# Sheet_1_2022-03-10.net
KiCad netlist of a schematic drawn in Altium Designer
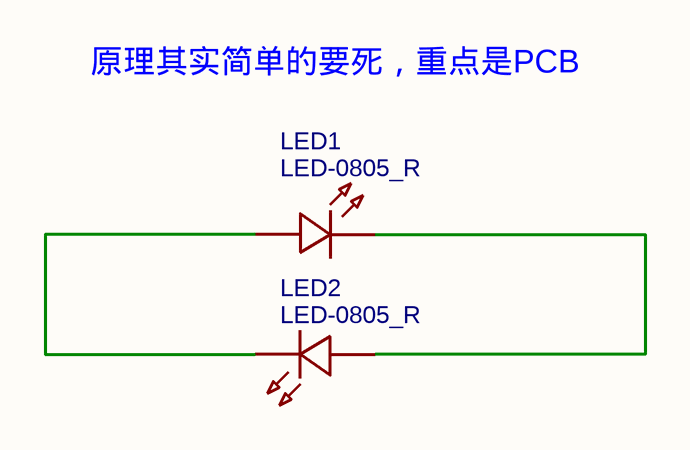
[diagram p0: Sheet_1_2022-03-10.schdoc]

(export (version "E")
  (design (tool "Eeschema 10.0.6"))
  (components
    (comp (ref "LED1")
      (value "LED-0805_R")
      (fields
        (field (name "BOM_MANUFACTURER PART") "17-21SURC/S530-A3/TR8")
        (field (name "BOM_SUPPLIER PART") "C72037")
        (field (name "CONTRIBUTOR") "LCEDA_Lib")
      )
      (libsource (lib "altium-import") (part "root_0_LED-0805_R_"))
    )
    (comp (ref "LED2")
      (value "LED-0805_R")
      (fields
        (field (name "BOM_MANUFACTURER PART") "17-21SURC/S530-A3/TR8")
        (field (name "BOM_SUPPLIER PART") "C72037")
        (field (name "CONTRIBUTOR") "LCEDA_Lib")
      )
      (libsource (lib "altium-import") (part "root_2_LED-0805_R_"))
    )
  )
  (nets
    (net (code "1") (name "Net-(LED1-Pad1)") (class "Default")
      (node (ref "LED1") (pin "1") (pinfunction "1_1") (pintype "passive"))
      (node (ref "LED2") (pin "2") (pinfunction "2_2") (pintype "passive"))
    )
    (net (code "2") (name "Net-(LED1-Pad2)") (class "Default")
      (node (ref "LED1") (pin "2") (pinfunction "2_2") (pintype "passive"))
      (node (ref "LED2") (pin "1") (pinfunction "1_1") (pintype "passive"))
    )
  )
)
